# jphy_v2.net
KiCad netlist of a schematic drawn in EAGLE
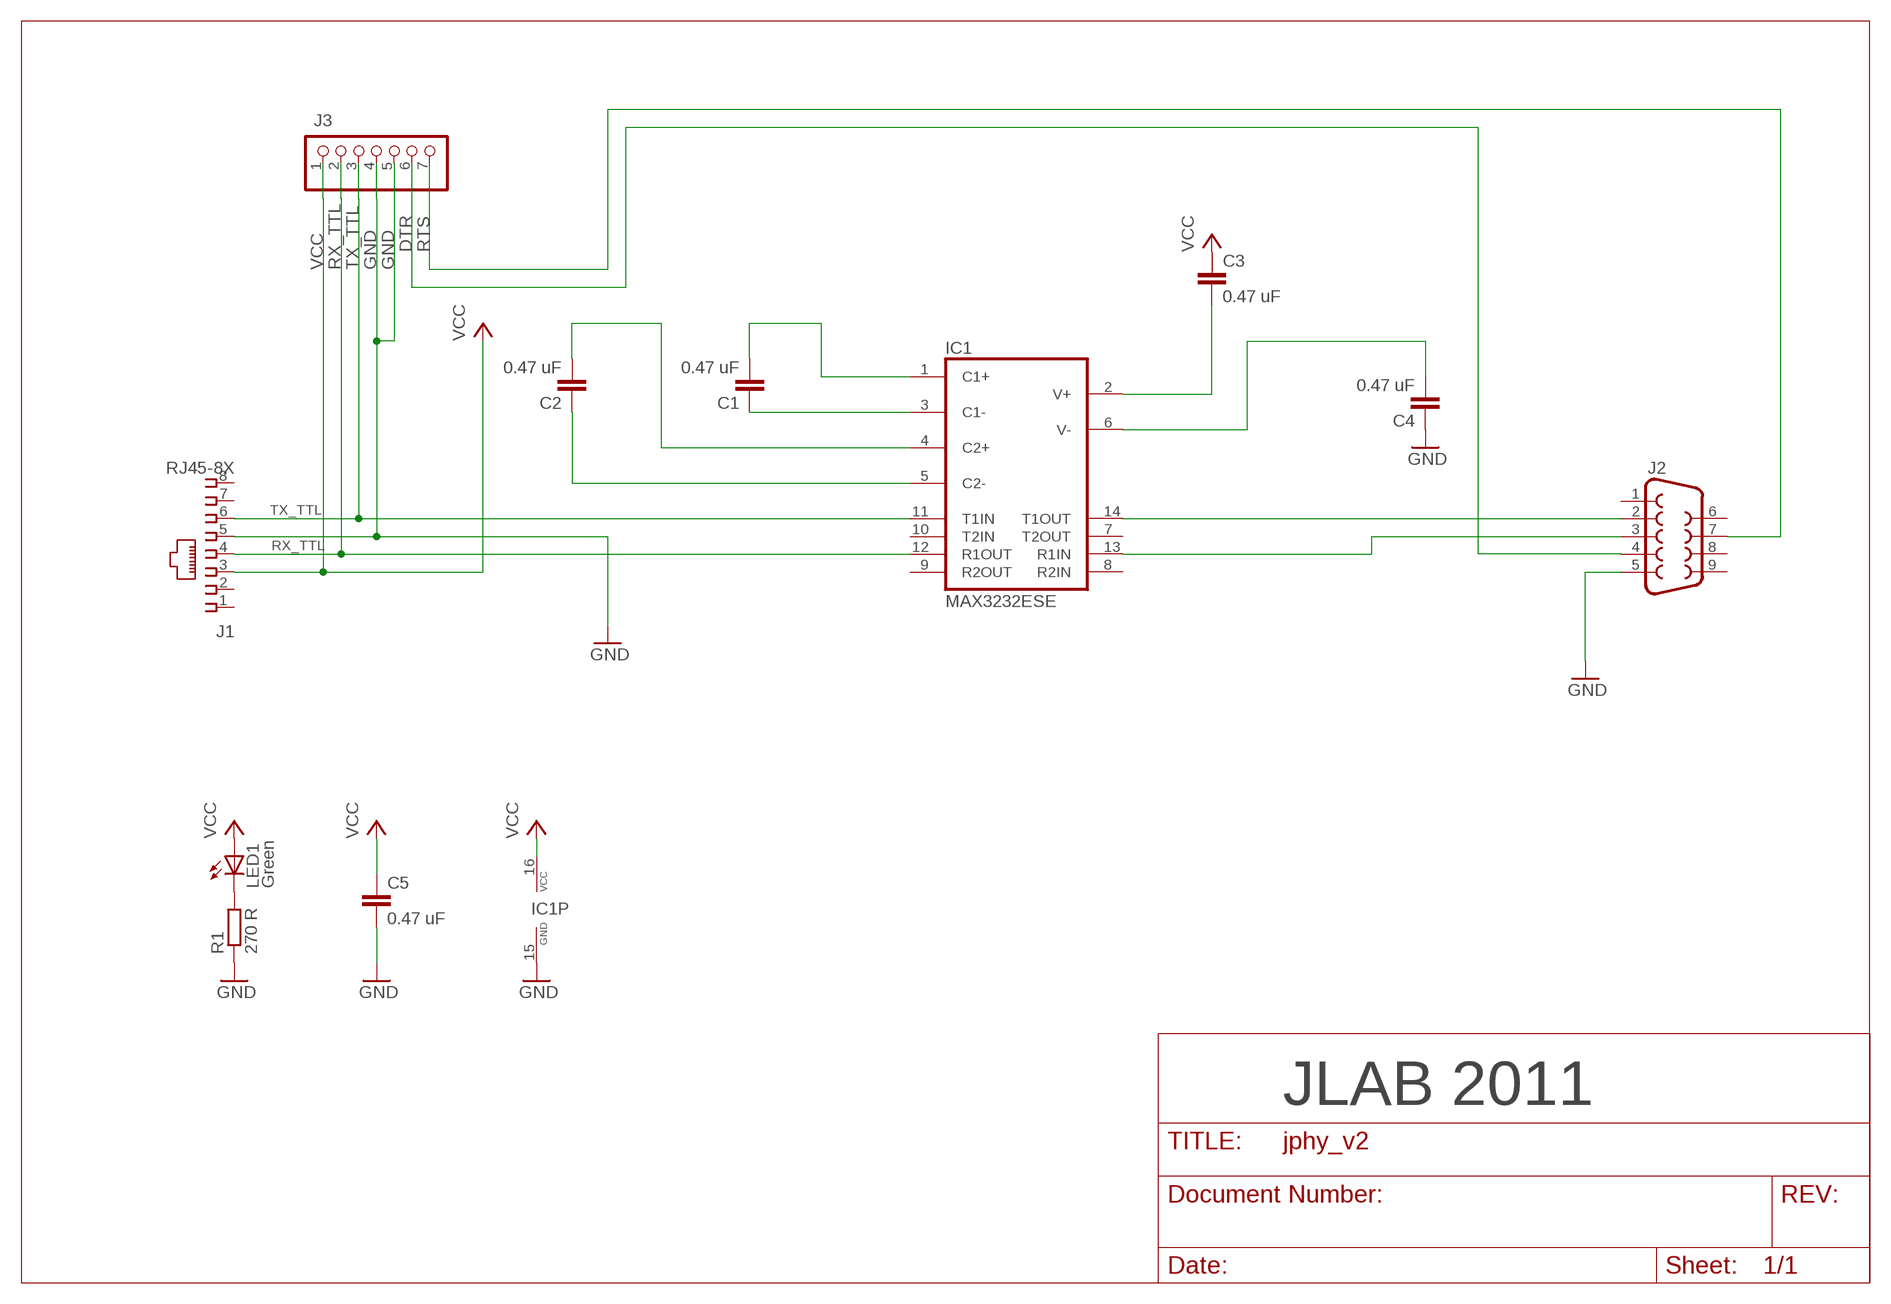
[diagram p0: schematic, sheet 1]

(export (version "E")
  (design (tool "Eeschema 10.0.6"))
  (components
    (comp (ref "C1")
      (value "0.47 uF")
      (footprint "eagle-import:C1206")
      (libsource (lib "eagle-import") (part "C-EUC1206"))
    )
    (comp (ref "C2")
      (value "0.47 uF")
      (footprint "eagle-import:C1206")
      (libsource (lib "eagle-import") (part "C-EUC1206"))
    )
    (comp (ref "C3")
      (value "0.47 uF")
      (footprint "eagle-import:C1206")
      (libsource (lib "eagle-import") (part "C-EUC1206"))
    )
    (comp (ref "C4")
      (value "0.47 uF")
      (footprint "eagle-import:C1206")
      (libsource (lib "eagle-import") (part "C-EUC1206"))
    )
    (comp (ref "C5")
      (value "0.47 uF")
      (footprint "eagle-import:C1206")
      (libsource (lib "eagle-import") (part "C-EUC1206"))
    )
    (comp (ref "IC1")
      (value "MAX3232ESE")
      (footprint "eagle-import:SO16")
      (fields (field (name "MF") "MAXIM"))
      (libsource (lib "eagle-import") (part "MAX3232SEE"))
    )
    (comp (ref "J1")
      (value "RJ45-8X")
      (footprint "eagle-import:RJ45-NO-SHIELD")
      (libsource (lib "eagle-import") (part "RJ45-8X"))
    )
    (comp (ref "J2")
      (value "F09D")
      (footprint "eagle-import:F09D")
      (libsource (lib "eagle-import") (part "F09D"))
    )
    (comp (ref "J3")
      (value "PINHD-1X7")
      (footprint "eagle-import:1X07")
      (libsource (lib "eagle-import") (part "PINHD-1X7"))
    )
    (comp (ref "LED1")
      (value "Green")
      (footprint "eagle-import:LED3MM")
      (libsource (lib "eagle-import") (part "LED3MM"))
    )
    (comp (ref "R1")
      (value "270 R")
      (footprint "eagle-import:0207_10")
      (libsource (lib "eagle-import") (part "R-EU_0207/10"))
    )
  )
  (nets
    (net (code "1") (name "/DTR") (class "Default")
      (node (ref "J2") (pin "4") (pinfunction "4_4") (pintype "passive"))
      (node (ref "J3") (pin "6") (pinfunction "6_6") (pintype "passive"))
    )
    (net (code "2") (name "/RTS") (class "Default")
      (node (ref "J2") (pin "7") (pinfunction "7_7") (pintype "passive"))
      (node (ref "J3") (pin "7") (pinfunction "7_7") (pintype "passive"))
    )
    (net (code "3") (name "/RX_TTL") (class "Default")
      (node (ref "IC1") (pin "12") (pinfunction "R1OUT_12") (pintype "output"))
      (node (ref "J1") (pin "4") (pinfunction "4_4") (pintype "passive"))
      (node (ref "J3") (pin "2") (pinfunction "2_2") (pintype "passive"))
    )
    (net (code "4") (name "/TX_TTL") (class "Default")
      (node (ref "IC1") (pin "11") (pinfunction "T1IN_11") (pintype "input"))
      (node (ref "J1") (pin "6") (pinfunction "6_6") (pintype "passive"))
      (node (ref "J3") (pin "3") (pinfunction "3_3") (pintype "passive"))
    )
    (net (code "5") (name "GND") (class "Default")
      (node (ref "C4") (pin "1") (pinfunction "1_1") (pintype "passive"))
      (node (ref "C5") (pin "2") (pinfunction "2_2") (pintype "passive"))
      (node (ref "IC1") (pin "15") (pinfunction "GND_15") (pintype "power_in"))
      (node (ref "J1") (pin "5") (pinfunction "5_5") (pintype "passive"))
      (node (ref "J2") (pin "5") (pinfunction "5_5") (pintype "passive"))
      (node (ref "J3") (pin "4") (pinfunction "4_4") (pintype "passive"))
      (node (ref "J3") (pin "5") (pinfunction "5_5") (pintype "passive"))
      (node (ref "R1") (pin "1") (pinfunction "1_1") (pintype "passive"))
    )
    (net (code "6") (name "Net-(IC1A-C1+)") (class "Default")
      (node (ref "C1") (pin "2") (pinfunction "2_2") (pintype "passive"))
      (node (ref "IC1") (pin "1") (pinfunction "C1+_1") (pintype "bidirectional"))
    )
    (net (code "7") (name "Net-(IC1A-C1-)") (class "Default")
      (node (ref "C1") (pin "1") (pinfunction "1_1") (pintype "passive"))
      (node (ref "IC1") (pin "3") (pinfunction "C1-_3") (pintype "bidirectional"))
    )
    (net (code "8") (name "Net-(IC1A-C2+)") (class "Default")
      (node (ref "C2") (pin "2") (pinfunction "2_2") (pintype "passive"))
      (node (ref "IC1") (pin "4") (pinfunction "C2+_4") (pintype "bidirectional"))
    )
    (net (code "9") (name "Net-(IC1A-C2-)") (class "Default")
      (node (ref "C2") (pin "1") (pinfunction "1_1") (pintype "passive"))
      (node (ref "IC1") (pin "5") (pinfunction "C2-_5") (pintype "bidirectional"))
    )
    (net (code "10") (name "Net-(IC1A-R1IN)") (class "Default")
      (node (ref "IC1") (pin "13") (pinfunction "R1IN_13") (pintype "input"))
      (node (ref "J2") (pin "3") (pinfunction "3_3") (pintype "passive"))
    )
    (net (code "11") (name "Net-(IC1A-T1OUT)") (class "Default")
      (node (ref "IC1") (pin "14") (pinfunction "T1OUT_14") (pintype "output"))
      (node (ref "J2") (pin "2") (pinfunction "2_2") (pintype "passive"))
    )
    (net (code "12") (name "Net-(IC1A-V+)") (class "Default")
      (node (ref "C3") (pin "2") (pinfunction "2_2") (pintype "passive"))
      (node (ref "IC1") (pin "2") (pinfunction "V+_2") (pintype "bidirectional"))
    )
    (net (code "13") (name "Net-(IC1A-V-)") (class "Default")
      (node (ref "C4") (pin "2") (pinfunction "2_2") (pintype "passive"))
      (node (ref "IC1") (pin "6") (pinfunction "V-_6") (pintype "bidirectional"))
    )
    (net (code "14") (name "Net-(LED1-C)") (class "Default")
      (node (ref "LED1") (pin "K") (pinfunction "C_K") (pintype "passive"))
      (node (ref "R1") (pin "2") (pinfunction "2_2") (pintype "passive"))
    )
    (net (code "15") (name "VCC") (class "Default")
      (node (ref "C3") (pin "1") (pinfunction "1_1") (pintype "passive"))
      (node (ref "C5") (pin "1") (pinfunction "1_1") (pintype "passive"))
      (node (ref "IC1") (pin "16") (pinfunction "VCC_16") (pintype "power_in"))
      (node (ref "J1") (pin "3") (pinfunction "3_3") (pintype "passive"))
      (node (ref "J3") (pin "1") (pinfunction "1_1") (pintype "passive"))
      (node (ref "LED1") (pin "A") (pinfunction "A_A") (pintype "passive"))
    )
    (net (code "16") (name "unconnected-(IC1A-R2IN-Pad8)") (class "Default")
      (node (ref "IC1") (pin "8") (pinfunction "R2IN_8") (pintype "input"))
    )
    (net (code "17") (name "unconnected-(IC1A-R2OUT-Pad9)") (class "Default")
      (node (ref "IC1") (pin "9") (pinfunction "R2OUT_9") (pintype "output"))
    )
    (net (code "18") (name "unconnected-(IC1A-T2IN-Pad10)") (class "Default")
      (node (ref "IC1") (pin "10") (pinfunction "T2IN_10") (pintype "input"))
    )
    (net (code "19") (name "unconnected-(IC1A-T2OUT-Pad7)") (class "Default")
      (node (ref "IC1") (pin "7") (pinfunction "T2OUT_7") (pintype "output"))
    )
    (net (code "20") (name "unconnected-(J1-Pad1)") (class "Default")
      (node (ref "J1") (pin "1") (pinfunction "1_1") (pintype "passive"))
    )
    (net (code "21") (name "unconnected-(J1-Pad2)") (class "Default")
      (node (ref "J1") (pin "2") (pinfunction "2_2") (pintype "passive"))
    )
    (net (code "22") (name "unconnected-(J1-Pad7)") (class "Default")
      (node (ref "J1") (pin "7") (pinfunction "7_7") (pintype "passive"))
    )
    (net (code "23") (name "unconnected-(J1-Pad8)") (class "Default")
      (node (ref "J1") (pin "8") (pinfunction "8_8") (pintype "passive"))
    )
    (net (code "24") (name "unconnected-(J2-Pad1)") (class "Default")
      (node (ref "J2") (pin "1") (pinfunction "1_1") (pintype "passive"))
    )
    (net (code "25") (name "unconnected-(J2-Pad6)") (class "Default")
      (node (ref "J2") (pin "6") (pinfunction "6_6") (pintype "passive"))
    )
    (net (code "26") (name "unconnected-(J2-Pad8)") (class "Default")
      (node (ref "J2") (pin "8") (pinfunction "8_8") (pintype "passive"))
    )
    (net (code "27") (name "unconnected-(J2-Pad9)") (class "Default")
      (node (ref "J2") (pin "9") (pinfunction "9_9") (pintype "passive"))
    )
  )
)
